# design.net
KiCad netlist of a schematic drawn in EasyEDA Pro
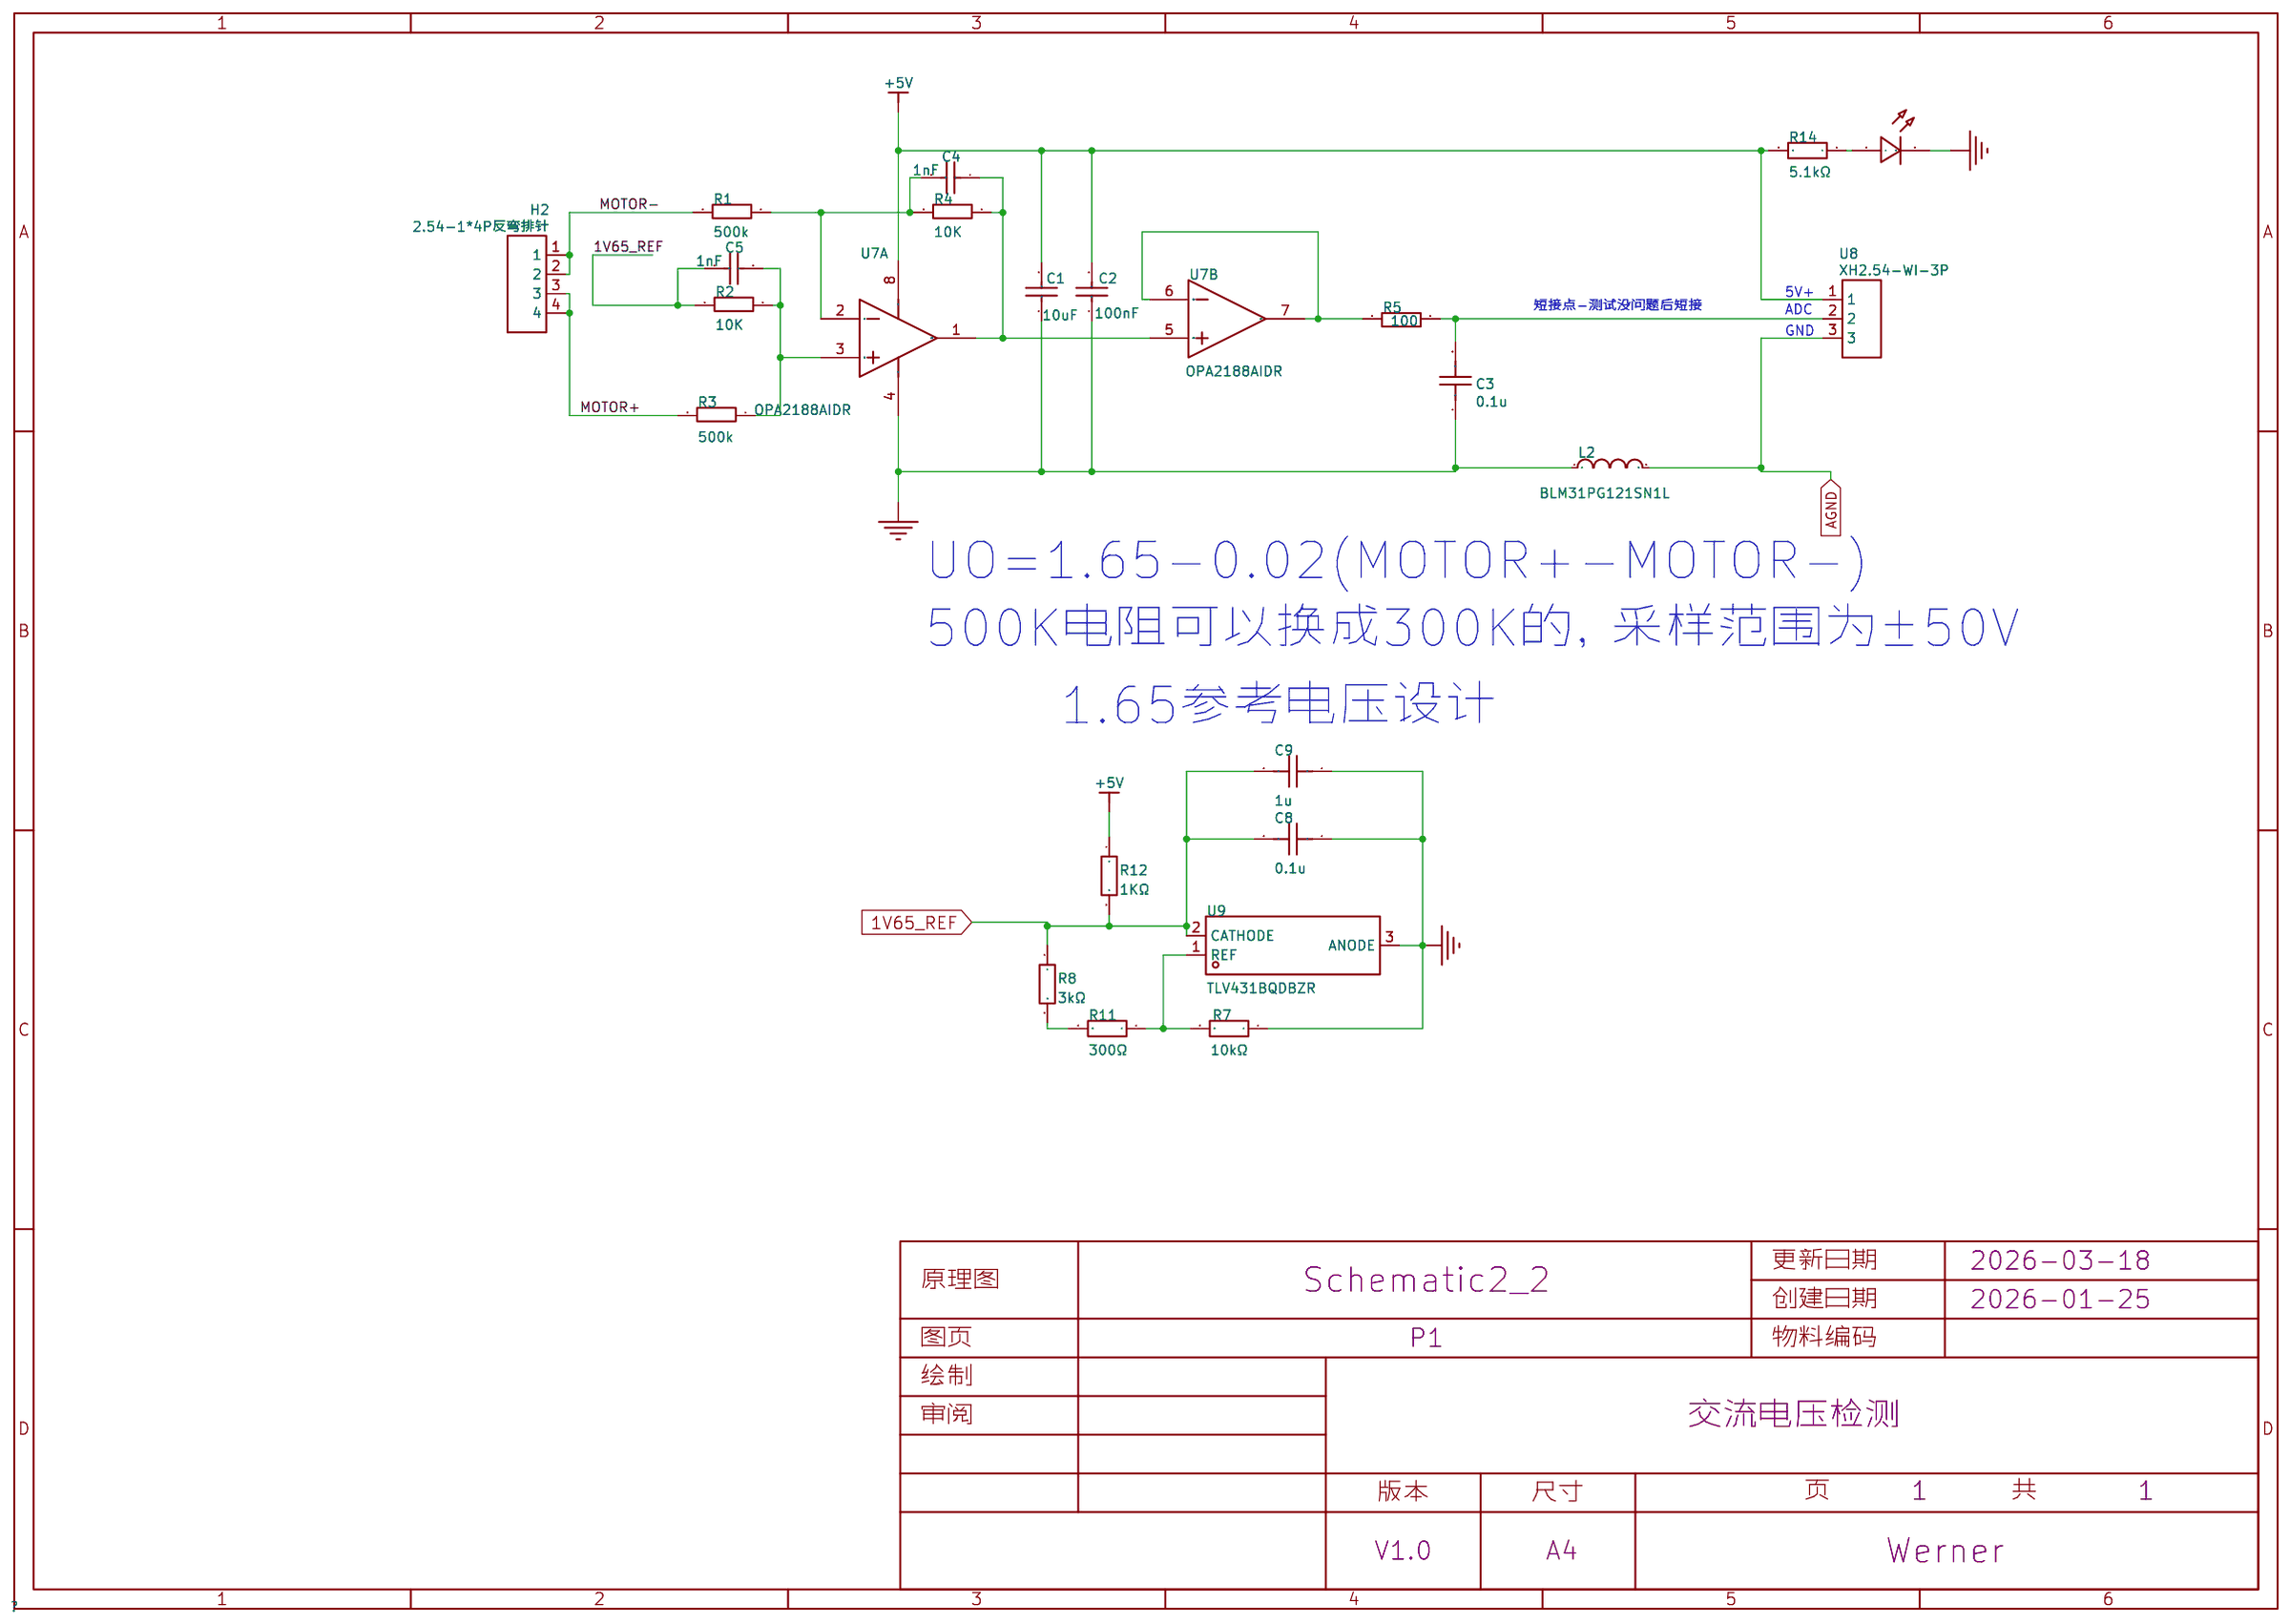
[diagram p0: schematic sheet]

(export (version "E")
  (design (tool "Eeschema 10.0.6"))
  (components
    (comp (ref "1.65V2")
      (value "~")
      (footprint "easyedapro:LED_0603")
      (libsource (lib "easyedapro") (part "LED_R"))
    )
    (comp (ref "C1")
      (value "10uF")
      (footprint "easyedapro:C0805")
      (fields (field (name "Manufacturer Part") "0805B104K500NT") (field (name "Manufacturer") "FH(风华)"))
      (libsource (lib "easyedapro") (part "0805B104K500NT"))
    )
    (comp (ref "C2")
      (value "100nF")
      (footprint "easyedapro:C0805")
      (fields (field (name "Manufacturer Part") "0805B104K500NT") (field (name "Manufacturer") "FH(风华)"))
      (libsource (lib "easyedapro") (part "0805B104K500NT"))
    )
    (comp (ref "C3")
      (value "0.1u")
      (footprint "easyedapro:C0603_2")
      (libsource (lib "easyedapro") (part "0.1u"))
    )
    (comp (ref "C4")
      (value "1nF")
      (footprint "easyedapro:C0805")
      (description "容值:100nF;精度:±10%;额定电压:50V;材质(温度系数):X7R;")
      (fields (field (name "Manufacturer Part") "0805B104K500NT") (field (name "Manufacturer") "FH(风华)"))
      (libsource (lib "easyedapro") (part "0805B104K500NT"))
    )
    (comp (ref "C5")
      (value "1nF")
      (footprint "easyedapro:C0805")
      (description "容值:100nF;精度:±10%;额定电压:50V;材质(温度系数):X7R;")
      (fields (field (name "Manufacturer Part") "0805B104K500NT") (field (name "Manufacturer") "FH(风华)"))
      (libsource (lib "easyedapro") (part "0805B104K500NT"))
    )
    (comp (ref "C8")
      (value "0.1u")
      (footprint "easyedapro:C0603_2")
      (libsource (lib "easyedapro") (part "0.1u"))
    )
    (comp (ref "C9")
      (value "1u")
      (footprint "easyedapro:C0603_2")
      (libsource (lib "easyedapro") (part "0.1u"))
    )
    (comp (ref "H2")
      (value "2.54-1*4P反弯排针")
      (footprint "easyedapro:HDR-TH_4P-P2.54-H-M-W10.4")
      (fields (field (name "Manufacturer") "BOOMELE(博穆精密)"))
      (libsource (lib "easyedapro") (part "2.54-1*4P反弯排针"))
    )
    (comp (ref "L2")
      (value "BLM31PG121SN1L")
      (footprint "easyedapro:L1206")
      (fields (field (name "Manufacturer") "muRata(村田)"))
      (libsource (lib "easyedapro") (part "BLM31PG121SN1L"))
    )
    (comp (ref "R1") (value "500k") (libsource (lib "easyedapro") (part "10K")))
    (comp (ref "R2") (value "10K") (libsource (lib "easyedapro") (part "1K")))
    (comp (ref "R3") (value "500k") (libsource (lib "easyedapro") (part "10K")))
    (comp (ref "R4") (value "10K") (libsource (lib "easyedapro") (part "4.7K")))
    (comp (ref "R5") (value "100") (libsource (lib "easyedapro") (part "4.7K")))
    (comp (ref "R7")
      (value "10kΩ")
      (footprint "easyedapro:R0805")
      (fields
        (field (name "Manufacturer Part") "0805W8F5101T5E")
        (field (name "Manufacturer") "UNI-ROYAL(厚声)")
      )
      (libsource (lib "easyedapro") (part "0805W8F5101T5E"))
    )
    (comp (ref "R8")
      (value "3kΩ")
      (footprint "easyedapro:R0805")
      (fields
        (field (name "Manufacturer Part") "0805W8F5101T5E")
        (field (name "Manufacturer") "UNI-ROYAL(厚声)")
      )
      (libsource (lib "easyedapro") (part "0805W8F5101T5E"))
    )
    (comp (ref "R11")
      (value "300Ω")
      (footprint "easyedapro:R0805")
      (fields
        (field (name "Manufacturer Part") "0805W8F5101T5E")
        (field (name "Manufacturer") "UNI-ROYAL(厚声)")
      )
      (libsource (lib "easyedapro") (part "0805W8F5101T5E"))
    )
    (comp (ref "R12")
      (value "1KΩ")
      (footprint "easyedapro:R0805")
      (fields
        (field (name "Manufacturer Part") "0805W8F5101T5E")
        (field (name "Manufacturer") "UNI-ROYAL(厚声)")
      )
      (libsource (lib "easyedapro") (part "0805W8F5101T5E"))
    )
    (comp (ref "R14")
      (value "5.1kΩ")
      (footprint "easyedapro:R0805")
      (fields
        (field (name "Manufacturer Part") "0805W8F5101T5E")
        (field (name "Manufacturer") "UNI-ROYAL(厚声)")
      )
      (libsource (lib "easyedapro") (part "0805W8F5101T5E"))
    )
    (comp (ref "U7")
      (value "OPA2188AIDR")
      (footprint "easyedapro:SOIC-8_L4.9-W3.9-P1.27-LS6.0-BL_1")
      (fields (field (name "Manufacturer") "TI(德州仪器)"))
      (libsource (lib "easyedapro") (part "OPA2188AIDR"))
    )
    (comp (ref "U8")
      (value "XH2.54-WI-3P")
      (footprint "easyedapro:CONN-TH_XH2.54-WI-3P")
      (libsource (lib "easyedapro") (part "XH2.54-WI-3P"))
    )
    (comp (ref "U9")
      (value "TLV431BQDBZR")
      (footprint "easyedapro:SOT-23-3_L2.9-W1.3-P0.95-LS2.4-BR")
      (fields (field (name "Manufacturer") "TI(德州仪器)"))
      (libsource (lib "easyedapro") (part "TLV431BQDBZR"))
    )
  )
  (nets
    (net (code "1") (name "+5V") (class "Default")
      (node (ref "C1") (pin "2") (pinfunction "2_2") (pintype "input"))
      (node (ref "C2") (pin "2") (pinfunction "2_2") (pintype "input"))
      (node (ref "R12") (pin "1") (pinfunction "1_1") (pintype "input"))
      (node (ref "R14") (pin "2") (pinfunction "2_2") (pintype "input"))
      (node (ref "U7") (pin "8") (pinfunction "V+_8") (pintype "unspecified"))
      (node (ref "U8") (pin "1") (pinfunction "1_1") (pintype "unspecified"))
    )
    (net (code "2") (name "/MOTOR+") (class "Default")
      (node (ref "H2") (pin "3") (pinfunction "3_3") (pintype "unspecified"))
      (node (ref "H2") (pin "4") (pinfunction "4_4") (pintype "unspecified"))
      (node (ref "R3") (pin "2") (pintype "unspecified"))
    )
    (net (code "3") (name "/MOTOR-") (class "Default")
      (node (ref "H2") (pin "1") (pinfunction "1_1") (pintype "unspecified"))
      (node (ref "H2") (pin "2") (pinfunction "2_2") (pintype "unspecified"))
      (node (ref "R1") (pin "2") (pintype "unspecified"))
    )
    (net (code "4") (name "1V65_REF") (class "Default")
      (node (ref "C5") (pin "2") (pinfunction "2_2") (pintype "input"))
      (node (ref "C8") (pin "2") (pinfunction "2_2") (pintype "unspecified"))
      (node (ref "C9") (pin "2") (pinfunction "2_2") (pintype "unspecified"))
      (node (ref "R12") (pin "2") (pinfunction "2_2") (pintype "input"))
      (node (ref "R2") (pin "2") (pintype "unspecified"))
      (node (ref "R8") (pin "1") (pinfunction "1_1") (pintype "input"))
      (node (ref "U9") (pin "2") (pinfunction "CATHODE_2") (pintype "unspecified"))
    )
    (net (code "5") (name "AGND") (class "Default")
      (node (ref "L2") (pin "2") (pinfunction "2_2") (pintype "unspecified"))
      (node (ref "U8") (pin "3") (pinfunction "3_3") (pintype "unspecified"))
    )
    (net (code "6") (name "GND") (class "Default")
      (node (ref "1.65V2") (pin "1") (pinfunction "C_1") (pintype "input"))
      (node (ref "C1") (pin "1") (pinfunction "1_1") (pintype "input"))
      (node (ref "C2") (pin "1") (pinfunction "1_1") (pintype "input"))
      (node (ref "C3") (pin "1") (pinfunction "1_1") (pintype "unspecified"))
      (node (ref "C8") (pin "1") (pinfunction "1_1") (pintype "unspecified"))
      (node (ref "C9") (pin "1") (pinfunction "1_1") (pintype "unspecified"))
      (node (ref "L2") (pin "1") (pinfunction "1_1") (pintype "unspecified"))
      (node (ref "R7") (pin "1") (pinfunction "1_1") (pintype "input"))
      (node (ref "U7") (pin "4") (pinfunction "V-_4") (pintype "unspecified"))
      (node (ref "U9") (pin "3") (pinfunction "ANODE_3") (pintype "unspecified"))
    )
    (net (code "7") (name "Net-(1.65V2-A)") (class "Default")
      (node (ref "1.65V2") (pin "2") (pinfunction "A_2") (pintype "input"))
      (node (ref "R14") (pin "1") (pinfunction "1_1") (pintype "input"))
    )
    (net (code "8") (name "Net-(C3-Pad2)") (class "Default")
      (node (ref "C3") (pin "2") (pinfunction "2_2") (pintype "unspecified"))
      (node (ref "R5") (pin "2") (pintype "unspecified"))
      (node (ref "U8") (pin "2") (pinfunction "2_2") (pintype "unspecified"))
    )
    (net (code "9") (name "Net-(R11-Pad2)") (class "Default")
      (node (ref "R11") (pin "2") (pinfunction "2_2") (pintype "input"))
      (node (ref "R8") (pin "2") (pinfunction "2_2") (pintype "input"))
    )
    (net (code "10") (name "Net-(U7A-IN_A+)") (class "Default")
      (node (ref "C5") (pin "1") (pinfunction "1_1") (pintype "input"))
      (node (ref "R2") (pin "1") (pintype "unspecified"))
      (node (ref "R3") (pin "1") (pintype "unspecified"))
      (node (ref "U7") (pin "3") (pinfunction "IN_A+_3") (pintype "unspecified"))
    )
    (net (code "11") (name "Net-(U7A-IN_A-)") (class "Default")
      (node (ref "C4") (pin "2") (pinfunction "2_2") (pintype "input"))
      (node (ref "R1") (pin "1") (pintype "unspecified"))
      (node (ref "R4") (pin "2") (pintype "unspecified"))
      (node (ref "U7") (pin "2") (pinfunction "IN_A-_2") (pintype "unspecified"))
    )
    (net (code "12") (name "Net-(U7A-OUT_A)") (class "Default")
      (node (ref "C4") (pin "1") (pinfunction "1_1") (pintype "input"))
      (node (ref "R4") (pin "1") (pintype "unspecified"))
      (node (ref "U7") (pin "1") (pinfunction "OUT_A_1") (pintype "output"))
      (node (ref "U7") (pin "5") (pinfunction "IN_B+_5") (pintype "unspecified"))
    )
    (net (code "13") (name "Net-(U7B-IN_B-)") (class "Default")
      (node (ref "R5") (pin "1") (pintype "unspecified"))
      (node (ref "U7") (pin "6") (pinfunction "IN_B-_6") (pintype "unspecified"))
      (node (ref "U7") (pin "7") (pinfunction "OUT_B_7") (pintype "output"))
    )
    (net (code "14") (name "Net-(U9-REF)") (class "Default")
      (node (ref "R11") (pin "1") (pinfunction "1_1") (pintype "input"))
      (node (ref "R7") (pin "2") (pinfunction "2_2") (pintype "input"))
      (node (ref "U9") (pin "1") (pinfunction "REF_1") (pintype "unspecified"))
    )
  )
)
